# Sheet1.net
KiCad netlist of a schematic drawn in Altium Designer
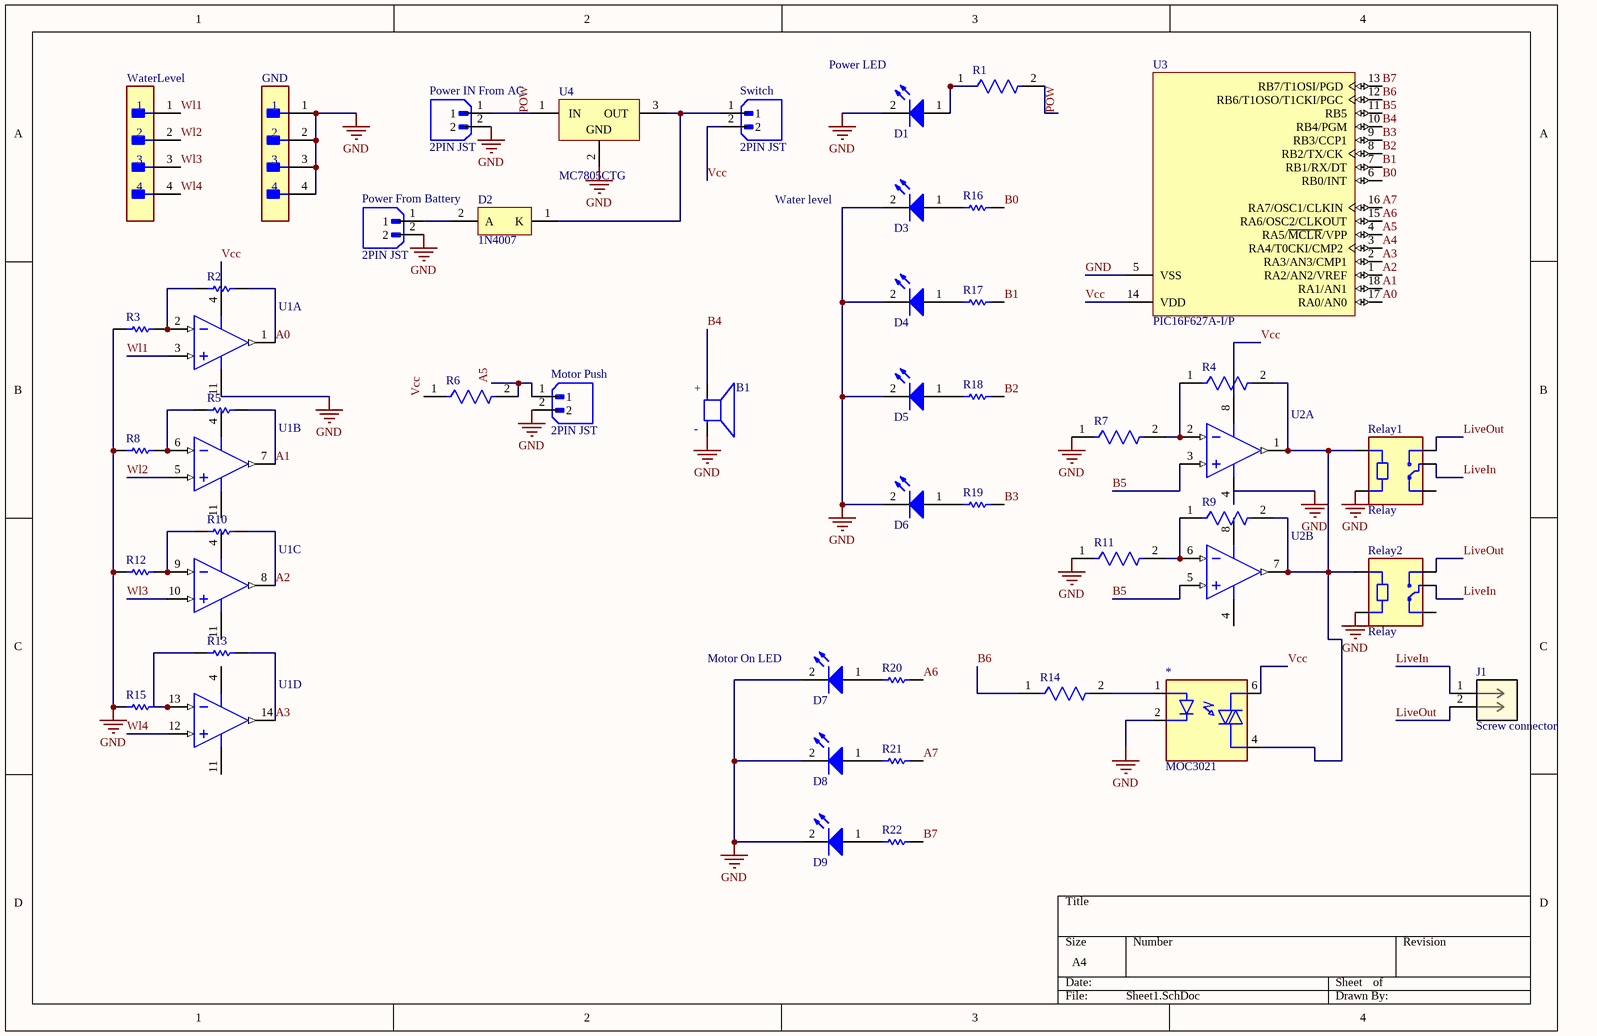
[diagram p0: Sheet1.SchDoc]

(export (version "E")
  (design (tool "Eeschema 10.0.6"))
  (components
    (comp (ref "*") (value "MOC3021") (footprint "MOC3021") (libsource (lib "Analogprj") (part "MOC3021")))
    (comp (ref "B1") (value "Buzzer") (footprint "Buzzer") (libsource (lib "Analogprj") (part "Buzzer")))
    (comp (ref "D1")
      (value "151051BS04000")
      (footprint "WL-TMRC_D5.9H8.7")
      (libsource (lib "Altium Content Vault") (part "LED_Blue_1A-2K"))
    )
    (comp (ref "D2")
      (value "1N4007")
      (footprint "ONSC-AXIAL_LEAD-2-59-10_P")
      (description "Standard Recovery Rectifier, 2-Pin Axial_Lead, Pb-Free, Bulk Bag")
      (fields (field (name "MANUFACTURER") "On Semiconductor"))
      (libsource (lib "Altium Content Vault") (part "ONSC-D-K1A2-2_A"))
    )
    (comp (ref "D3")
      (value "151051BS04000")
      (footprint "WL-TMRC_D5.9H8.7")
      (libsource (lib "Altium Content Vault") (part "LED_Blue_1A-2K"))
    )
    (comp (ref "D4")
      (value "151051BS04000")
      (footprint "WL-TMRC_D5.9H8.7")
      (libsource (lib "Altium Content Vault") (part "LED_Blue_1A-2K"))
    )
    (comp (ref "D5")
      (value "151051BS04000")
      (footprint "WL-TMRC_D5.9H8.7")
      (libsource (lib "Altium Content Vault") (part "LED_Blue_1A-2K"))
    )
    (comp (ref "D6")
      (value "151051BS04000")
      (footprint "WL-TMRC_D5.9H8.7")
      (libsource (lib "Altium Content Vault") (part "LED_Blue_1A-2K"))
    )
    (comp (ref "D7")
      (value "151051BS04000")
      (footprint "WL-TMRC_D5.9H8.7")
      (libsource (lib "Altium Content Vault") (part "LED_Blue_1A-2K"))
    )
    (comp (ref "D8")
      (value "151051BS04000")
      (footprint "WL-TMRC_D5.9H8.7")
      (libsource (lib "Altium Content Vault") (part "LED_Blue_1A-2K"))
    )
    (comp (ref "D9")
      (value "151051BS04000")
      (footprint "WL-TMRC_D5.9H8.7")
      (libsource (lib "Altium Content Vault") (part "LED_Blue_1A-2K"))
    )
    (comp (ref "GND")
      (value "B4B-XH-A(LF)(SN)")
      (footprint "FP-B4B-XH-A_LF_SN-MFG")
      (description "CONN HEADER VERT 4POS 2.5MM")
      (libsource (lib "Altium Content Vault") (part "299a8cea1bdcbc3624fe62c390fa72c"))
    )
    (comp (ref "J1")
      (value "Screw connector")
      (footprint "Screw Connector")
      (libsource (lib "Analogprj") (part "Screw connector"))
    )
    (comp (ref "Motor Push")
      (value "2PIN JST")
      (footprint "JST 2PIN")
      (libsource (lib "") (part "2PIN JST_1"))
    )
    (comp (ref "Power From Battery")
      (value "2PIN JST")
      (footprint "JST 2PIN")
      (libsource (lib "Analogprj") (part "2PIN JST"))
    )
    (comp (ref "Power IN From AC")
      (value "2PIN JST")
      (footprint "JST 2PIN")
      (libsource (lib "Analogprj") (part "2PIN JST"))
    )
    (comp (ref "R1")
      (value "MRS25000C1001FCT00")
      (footprint "FP-MRS25-MFG")
      (description "RES 1K OHM 0.6W 1% AXIAL")
      (fields (field (name "TOLERANCE") "1%"))
      (libsource (lib "Altium Content Vault") (part "1029c3af85768c4190bb7ad29bc67b5"))
    )
    (comp (ref "R2")
      (value "RC0805FR-071KL")
      (footprint "RESC2013X60X35ML10T20")
      (description "Chip Resistor, 1 KOhm, +/- 1%, 125 mW, -55 to 155 degC, 0805 (2012 Metric), RoHS, Tape and Reel")
      (fields (field (name "TOLERANCE") "1%") (field (name "MANUFACTURER") "Yageo"))
      (libsource (lib "Altium Content Vault") (part "RES-2"))
    )
    (comp (ref "R3")
      (value "RC0805FR-071KL")
      (footprint "RESC2013X60X35ML10T20")
      (description "Chip Resistor, 1 KOhm, +/- 1%, 125 mW, -55 to 155 degC, 0805 (2012 Metric), RoHS, Tape and Reel")
      (fields (field (name "TOLERANCE") "1%") (field (name "MANUFACTURER") "Yageo"))
      (libsource (lib "Altium Content Vault") (part "RES-2"))
    )
    (comp (ref "R4")
      (value "MRS25000C1001FCT00")
      (footprint "FP-MRS25-MFG")
      (description "RES 1K OHM 0.6W 1% AXIAL")
      (fields (field (name "TOLERANCE") "1%"))
      (libsource (lib "Altium Content Vault") (part "1029c3af85768c4190bb7ad29bc67b5"))
    )
    (comp (ref "R5")
      (value "RC0805FR-071KL")
      (footprint "RESC2013X60X35ML10T20")
      (description "Chip Resistor, 1 KOhm, +/- 1%, 125 mW, -55 to 155 degC, 0805 (2012 Metric), RoHS, Tape and Reel")
      (fields (field (name "TOLERANCE") "1%") (field (name "MANUFACTURER") "Yageo"))
      (libsource (lib "Altium Content Vault") (part "RES-2"))
    )
    (comp (ref "R6")
      (value "MRS25000C1001FCT00")
      (footprint "FP-MRS25-MFG")
      (description "100K")
      (fields (field (name "TOLERANCE") "1%"))
      (libsource (lib "Altium Content Vault") (part "1029c3af85768c4190bb7ad29bc67b5"))
    )
    (comp (ref "R7")
      (value "MRS25000C1001FCT00")
      (footprint "FP-MRS25-MFG")
      (description "RES 1K OHM 0.6W 1% AXIAL")
      (fields (field (name "TOLERANCE") "1%"))
      (libsource (lib "Altium Content Vault") (part "1029c3af85768c4190bb7ad29bc67b5"))
    )
    (comp (ref "R8")
      (value "RC0805FR-071KL")
      (footprint "RESC2013X60X35ML10T20")
      (description "Chip Resistor, 1 KOhm, +/- 1%, 125 mW, -55 to 155 degC, 0805 (2012 Metric), RoHS, Tape and Reel")
      (fields (field (name "TOLERANCE") "1%") (field (name "MANUFACTURER") "Yageo"))
      (libsource (lib "Altium Content Vault") (part "RES-2"))
    )
    (comp (ref "R9")
      (value "MRS25000C1001FCT00")
      (footprint "FP-MRS25-MFG")
      (description "RES 1K OHM 0.6W 1% AXIAL")
      (fields (field (name "TOLERANCE") "1%"))
      (libsource (lib "Altium Content Vault") (part "1029c3af85768c4190bb7ad29bc67b5"))
    )
    (comp (ref "R10")
      (value "RC0805FR-071KL")
      (footprint "RESC2013X60X35ML10T20")
      (description "Chip Resistor, 1 KOhm, +/- 1%, 125 mW, -55 to 155 degC, 0805 (2012 Metric), RoHS, Tape and Reel")
      (fields (field (name "TOLERANCE") "1%") (field (name "MANUFACTURER") "Yageo"))
      (libsource (lib "Altium Content Vault") (part "RES-2"))
    )
    (comp (ref "R11")
      (value "MRS25000C1001FCT00")
      (footprint "FP-MRS25-MFG")
      (description "RES 1K OHM 0.6W 1% AXIAL")
      (fields (field (name "TOLERANCE") "1%"))
      (libsource (lib "Altium Content Vault") (part "1029c3af85768c4190bb7ad29bc67b5"))
    )
    (comp (ref "R12")
      (value "RC0805FR-071KL")
      (footprint "RESC2013X60X35ML10T20")
      (description "Chip Resistor, 1 KOhm, +/- 1%, 125 mW, -55 to 155 degC, 0805 (2012 Metric), RoHS, Tape and Reel")
      (fields (field (name "TOLERANCE") "1%") (field (name "MANUFACTURER") "Yageo"))
      (libsource (lib "Altium Content Vault") (part "RES-2"))
    )
    (comp (ref "R13")
      (value "RC0805FR-071KL")
      (footprint "RESC2013X60X35ML10T20")
      (description "Chip Resistor, 1 KOhm, +/- 1%, 125 mW, -55 to 155 degC, 0805 (2012 Metric), RoHS, Tape and Reel")
      (fields (field (name "TOLERANCE") "1%") (field (name "MANUFACTURER") "Yageo"))
      (libsource (lib "Altium Content Vault") (part "RES-2"))
    )
    (comp (ref "R14")
      (value "MRS25000C1001FCT00")
      (footprint "FP-MRS25-MFG")
      (description "RES 1K OHM 0.6W 1% AXIAL")
      (fields (field (name "TOLERANCE") "1%"))
      (libsource (lib "Altium Content Vault") (part "1029c3af85768c4190bb7ad29bc67b5"))
    )
    (comp (ref "R15")
      (value "RC0805FR-071KL")
      (footprint "RESC2013X60X35ML10T20")
      (description "Chip Resistor, 1 KOhm, +/- 1%, 125 mW, -55 to 155 degC, 0805 (2012 Metric), RoHS, Tape and Reel")
      (fields (field (name "TOLERANCE") "1%") (field (name "MANUFACTURER") "Yageo"))
      (libsource (lib "Altium Content Vault") (part "RES-2"))
    )
    (comp (ref "R16")
      (value "RC0805FR-071KL")
      (footprint "RESC2013X60X35ML10T20")
      (description "Chip Resistor, 1 KOhm, +/- 1%, 125 mW, -55 to 155 degC, 0805 (2012 Metric), RoHS, Tape and Reel")
      (fields (field (name "TOLERANCE") "1%") (field (name "MANUFACTURER") "Yageo"))
      (libsource (lib "Altium Content Vault") (part "RES-2"))
    )
    (comp (ref "R17")
      (value "RC0805FR-071KL")
      (footprint "RESC2013X60X35ML10T20")
      (description "Chip Resistor, 1 KOhm, +/- 1%, 125 mW, -55 to 155 degC, 0805 (2012 Metric), RoHS, Tape and Reel")
      (fields (field (name "TOLERANCE") "1%") (field (name "MANUFACTURER") "Yageo"))
      (libsource (lib "Altium Content Vault") (part "RES-2"))
    )
    (comp (ref "R18")
      (value "RC0805FR-071KL")
      (footprint "RESC2013X60X35ML10T20")
      (description "Chip Resistor, 1 KOhm, +/- 1%, 125 mW, -55 to 155 degC, 0805 (2012 Metric), RoHS, Tape and Reel")
      (fields (field (name "TOLERANCE") "1%") (field (name "MANUFACTURER") "Yageo"))
      (libsource (lib "Altium Content Vault") (part "RES-2"))
    )
    (comp (ref "R19")
      (value "RC0805FR-071KL")
      (footprint "RESC2013X60X35ML10T20")
      (description "Chip Resistor, 1 KOhm, +/- 1%, 125 mW, -55 to 155 degC, 0805 (2012 Metric), RoHS, Tape and Reel")
      (fields (field (name "TOLERANCE") "1%") (field (name "MANUFACTURER") "Yageo"))
      (libsource (lib "Altium Content Vault") (part "RES-2"))
    )
    (comp (ref "R20")
      (value "RC0805FR-071KL")
      (footprint "RESC2013X60X35ML10T20")
      (description "Chip Resistor, 1 KOhm, +/- 1%, 125 mW, -55 to 155 degC, 0805 (2012 Metric), RoHS, Tape and Reel")
      (fields (field (name "TOLERANCE") "1%") (field (name "MANUFACTURER") "Yageo"))
      (libsource (lib "Altium Content Vault") (part "RES-2"))
    )
    (comp (ref "R21")
      (value "RC0805FR-071KL")
      (footprint "RESC2013X60X35ML10T20")
      (description "Chip Resistor, 1 KOhm, +/- 1%, 125 mW, -55 to 155 degC, 0805 (2012 Metric), RoHS, Tape and Reel")
      (fields (field (name "TOLERANCE") "1%") (field (name "MANUFACTURER") "Yageo"))
      (libsource (lib "Altium Content Vault") (part "RES-2"))
    )
    (comp (ref "R22")
      (value "RC0805FR-071KL")
      (footprint "RESC2013X60X35ML10T20")
      (description "Chip Resistor, 1 KOhm, +/- 1%, 125 mW, -55 to 155 degC, 0805 (2012 Metric), RoHS, Tape and Reel")
      (fields (field (name "TOLERANCE") "1%") (field (name "MANUFACTURER") "Yageo"))
      (libsource (lib "Altium Content Vault") (part "RES-2"))
    )
    (comp (ref "Relay1") (value "Relay") (footprint "Relay") (libsource (lib "Analogprj") (part "Relay")))
    (comp (ref "Relay2") (value "Relay") (footprint "Relay") (libsource (lib "Analogprj") (part "Relay")))
    (comp (ref "Switch") (value "2PIN JST") (footprint "JST 2PIN") (libsource (lib "") (part "2PIN JST_1")))
    (comp (ref "U1")
      (value "LMV324IDR")
      (footprint "D0014A_V")
      (libsource (lib "Altium Content Vault") (part "TI-LMV324-D-14"))
    )
    (comp (ref "U2")
      (value "LM358MX")
      (footprint "D0008A_M")
      (description "Low Power Dual Operational Amplifier, 8-pin Narrow SOIC")
      (fields (field (name "MANUFACTURER") "Texas Instruments"))
      (libsource (lib "Altium Content Vault") (part "AMP-OPA-LM158-8"))
    )
    (comp (ref "U3")
      (value "PIC16F627A-I/P")
      (footprint "PDIP300-P18")
      (libsource (lib "Altium Content Vault") (part "MC-8B-16F627A-IL18"))
    )
    (comp (ref "U4")
      (value "MC7805CTG")
      (footprint "ONSC-TO-220-3-221AB-01")
      (description "Positive Voltage Regulator, 1 A, 5 V, 0 to 125 degC, 3-Pin TO-220, RoHS, Tube")
      (fields (field (name "MANUFACTURER") "ON Semiconductor"))
      (libsource (lib "Altium Content Vault") (part "ONSC-MC7805CTG-TO-220-3"))
    )
    (comp (ref "WaterLevel")
      (value "B4B-XH-A(LF)(SN)")
      (footprint "FP-B4B-XH-A_LF_SN-MFG")
      (description "CONN HEADER VERT 4POS 2.5MM")
      (libsource (lib "Altium Content Vault") (part "299a8cea1bdcbc3624fe62c390fa72c"))
    )
  )
  (nets
    (net (code "1") (name "/A0") (class "Default")
      (node (ref "R2") (pin "2") (pinfunction "2_2") (pintype "passive"))
      (node (ref "U1") (pin "1") (pinfunction "1OUT_1") (pintype "output"))
      (node (ref "U3") (pin "17") (pinfunction "RA0/AN0_17") (pintype "bidirectional"))
    )
    (net (code "2") (name "/A1") (class "Default")
      (node (ref "R5") (pin "2") (pinfunction "2_2") (pintype "passive"))
      (node (ref "U1") (pin "7") (pinfunction "2OUT_7") (pintype "output"))
      (node (ref "U3") (pin "18") (pinfunction "RA1/AN1_18") (pintype "bidirectional"))
    )
    (net (code "3") (name "/A2") (class "Default")
      (node (ref "R10") (pin "2") (pinfunction "2_2") (pintype "passive"))
      (node (ref "U1") (pin "8") (pinfunction "3OUT_8") (pintype "output"))
      (node (ref "U3") (pin "1") (pinfunction "RA2/AN2/VREF_1") (pintype "bidirectional"))
    )
    (net (code "4") (name "/A3") (class "Default")
      (node (ref "R13") (pin "2") (pinfunction "2_2") (pintype "passive"))
      (node (ref "U1") (pin "14") (pinfunction "4OUT_14") (pintype "output"))
      (node (ref "U3") (pin "2") (pinfunction "RA3/AN3/CMP1_2") (pintype "bidirectional"))
    )
    (net (code "5") (name "/A4") (class "Default")
      (node (ref "U3") (pin "3") (pinfunction "RA4/T0CKI/CMP2_3") (pintype "bidirectional"))
    )
    (net (code "6") (name "/A5") (class "Default")
      (node (ref "Motor Push") (pin "1") (pinfunction "1_1") (pintype "passive"))
      (node (ref "R6") (pin "2") (pinfunction "2_2") (pintype "passive"))
      (node (ref "U3") (pin "4") (pinfunction "RA5/~{MCLR}/VPP_4") (pintype "bidirectional"))
    )
    (net (code "7") (name "/A6") (class "Default")
      (node (ref "R20") (pin "2") (pinfunction "2_2") (pintype "passive"))
      (node (ref "U3") (pin "15") (pinfunction "RA6/OSC2/CLKOUT_15") (pintype "bidirectional"))
    )
    (net (code "8") (name "/A7") (class "Default")
      (node (ref "R21") (pin "2") (pinfunction "2_2") (pintype "passive"))
      (node (ref "U3") (pin "16") (pinfunction "RA7/OSC1/CLKIN_16") (pintype "bidirectional"))
    )
    (net (code "9") (name "/B0") (class "Default")
      (node (ref "R16") (pin "2") (pinfunction "2_2") (pintype "passive"))
      (node (ref "U3") (pin "6") (pinfunction "RB0/INT_6") (pintype "bidirectional"))
    )
    (net (code "10") (name "/B1") (class "Default")
      (node (ref "R17") (pin "2") (pinfunction "2_2") (pintype "passive"))
      (node (ref "U3") (pin "7") (pinfunction "RB1/RX/DT_7") (pintype "bidirectional"))
    )
    (net (code "11") (name "/B2") (class "Default")
      (node (ref "R18") (pin "2") (pinfunction "2_2") (pintype "passive"))
      (node (ref "U3") (pin "8") (pinfunction "RB2/TX/CK_8") (pintype "bidirectional"))
    )
    (net (code "12") (name "/B3") (class "Default")
      (node (ref "R19") (pin "2") (pinfunction "2_2") (pintype "passive"))
      (node (ref "U3") (pin "9") (pinfunction "RB3/CCP1_9") (pintype "bidirectional"))
    )
    (net (code "13") (name "/B4") (class "Default")
      (node (ref "B1") (pin "P") (pinfunction "P_P") (pintype "passive"))
      (node (ref "U3") (pin "10") (pinfunction "RB4/PGM_10") (pintype "bidirectional"))
    )
    (net (code "14") (name "/B5") (class "Default")
      (node (ref "U2") (pin "3") (pinfunction "INA+_3") (pintype "input"))
      (node (ref "U2") (pin "5") (pinfunction "INB+_5") (pintype "input"))
      (node (ref "U3") (pin "11") (pinfunction "RB5_11") (pintype "bidirectional"))
    )
    (net (code "15") (name "/B6") (class "Default")
      (node (ref "R14") (pin "1") (pinfunction "1_1") (pintype "passive"))
      (node (ref "U3") (pin "12") (pinfunction "RB6/T1OSO/T1CKI/PGC_12") (pintype "bidirectional"))
    )
    (net (code "16") (name "/B7") (class "Default")
      (node (ref "R22") (pin "2") (pinfunction "2_2") (pintype "passive"))
      (node (ref "U3") (pin "13") (pinfunction "RB7/T1OSI/PGD_13") (pintype "bidirectional"))
    )
    (net (code "17") (name "/LiveIn") (class "Default")
      (node (ref "J1") (pin "1") (pinfunction "1_1") (pintype "passive"))
      (node (ref "Relay1") (pin "COM") (pinfunction "COM_COM") (pintype "passive"))
      (node (ref "Relay2") (pin "COM") (pinfunction "COM_COM") (pintype "passive"))
    )
    (net (code "18") (name "/LiveOut") (class "Default")
      (node (ref "J1") (pin "2") (pinfunction "2_2") (pintype "passive"))
      (node (ref "Relay1") (pin "NO") (pinfunction "NO_NO") (pintype "passive"))
      (node (ref "Relay2") (pin "NO") (pinfunction "NO_NO") (pintype "passive"))
    )
    (net (code "19") (name "/POW") (class "Default")
      (node (ref "Power IN From AC") (pin "1") (pinfunction "1_1") (pintype "passive"))
      (node (ref "R1") (pin "2") (pinfunction "2_2") (pintype "passive"))
      (node (ref "U4") (pin "1") (pinfunction "IN_1") (pintype "power_in"))
    )
    (net (code "20") (name "/Vcc") (class "Default")
      (node (ref "*") (pin "6") (pinfunction "MAIN_TERM1_6") (pintype "passive"))
      (node (ref "R6") (pin "1") (pinfunction "1_1") (pintype "passive"))
      (node (ref "Switch") (pin "2") (pinfunction "2_2") (pintype "passive"))
      (node (ref "U1") (pin "4") (pinfunction "VCC+_4") (pintype "power_in"))
      (node (ref "U2") (pin "8") (pinfunction "V+_8") (pintype "power_in"))
      (node (ref "U3") (pin "14") (pinfunction "VDD_14") (pintype "power_in"))
    )
    (net (code "21") (name "/Wl1") (class "Default")
      (node (ref "U1") (pin "3") (pinfunction "1IN+_3") (pintype "input"))
      (node (ref "WaterLevel") (pin "1") (pinfunction "1_1") (pintype "passive"))
    )
    (net (code "22") (name "/Wl2") (class "Default")
      (node (ref "U1") (pin "5") (pinfunction "2IN+_5") (pintype "input"))
      (node (ref "WaterLevel") (pin "2") (pinfunction "2_2") (pintype "passive"))
    )
    (net (code "23") (name "/Wl3") (class "Default")
      (node (ref "U1") (pin "10") (pinfunction "3IN+_10") (pintype "input"))
      (node (ref "WaterLevel") (pin "3") (pinfunction "3_3") (pintype "passive"))
    )
    (net (code "24") (name "/Wl4") (class "Default")
      (node (ref "U1") (pin "12") (pinfunction "4IN+_12") (pintype "input"))
      (node (ref "WaterLevel") (pin "4") (pinfunction "4_4") (pintype "passive"))
    )
    (net (code "25") (name "GND") (class "Default")
      (node (ref "*") (pin "2") (pinfunction "CATODE_2") (pintype "passive"))
      (node (ref "B1") (pin "N") (pinfunction "N_N") (pintype "passive"))
      (node (ref "D1") (pin "2") (pinfunction "K_2") (pintype "passive"))
      (node (ref "D3") (pin "2") (pinfunction "K_2") (pintype "passive"))
      (node (ref "D4") (pin "2") (pinfunction "K_2") (pintype "passive"))
      (node (ref "D5") (pin "2") (pinfunction "K_2") (pintype "passive"))
      (node (ref "D6") (pin "2") (pinfunction "K_2") (pintype "passive"))
      (node (ref "D7") (pin "2") (pinfunction "K_2") (pintype "passive"))
      (node (ref "D8") (pin "2") (pinfunction "K_2") (pintype "passive"))
      (node (ref "D9") (pin "2") (pinfunction "K_2") (pintype "passive"))
      (node (ref "GND") (pin "1") (pinfunction "1_1") (pintype "passive"))
      (node (ref "GND") (pin "2") (pinfunction "2_2") (pintype "passive"))
      (node (ref "GND") (pin "3") (pinfunction "3_3") (pintype "passive"))
      (node (ref "GND") (pin "4") (pinfunction "4_4") (pintype "passive"))
      (node (ref "Motor Push") (pin "2") (pinfunction "2_2") (pintype "passive"))
      (node (ref "Power From Battery") (pin "2") (pinfunction "2_2") (pintype "passive"))
      (node (ref "Power IN From AC") (pin "2") (pinfunction "2_2") (pintype "passive"))
      (node (ref "R11") (pin "1") (pinfunction "1_1") (pintype "passive"))
      (node (ref "R12") (pin "1") (pinfunction "1_1") (pintype "passive"))
      (node (ref "R15") (pin "1") (pinfunction "1_1") (pintype "passive"))
      (node (ref "R3") (pin "1") (pinfunction "1_1") (pintype "passive"))
      (node (ref "R7") (pin "1") (pinfunction "1_1") (pintype "passive"))
      (node (ref "R8") (pin "1") (pinfunction "1_1") (pintype "passive"))
      (node (ref "Relay1") (pin "A2") (pinfunction "A2_A2") (pintype "passive"))
      (node (ref "Relay2") (pin "A2") (pinfunction "A2_A2") (pintype "passive"))
      (node (ref "U1") (pin "11") (pinfunction "GND_11") (pintype "power_in"))
      (node (ref "U2") (pin "4") (pinfunction "GND_4") (pintype "power_in"))
      (node (ref "U3") (pin "5") (pinfunction "VSS_5") (pintype "power_in"))
      (node (ref "U4") (pin "2") (pinfunction "GND_2") (pintype "power_in"))
    )
    (net (code "26") (name "Net-(*-ANODE)") (class "Default")
      (node (ref "*") (pin "1") (pinfunction "ANODE_1") (pintype "passive"))
      (node (ref "R14") (pin "2") (pinfunction "2_2") (pintype "passive"))
    )
    (net (code "27") (name "Net-(*-MAIN_TERM2)") (class "Default")
      (node (ref "*") (pin "4") (pinfunction "MAIN_TERM2_4") (pintype "passive"))
      (node (ref "R4") (pin "2") (pinfunction "2_2") (pintype "passive"))
      (node (ref "R9") (pin "2") (pinfunction "2_2") (pintype "passive"))
      (node (ref "Relay1") (pin "A1") (pinfunction "A1_A1") (pintype "passive"))
      (node (ref "Relay2") (pin "A1") (pinfunction "A1_A1") (pintype "passive"))
      (node (ref "U2") (pin "1") (pinfunction "OUTA_1") (pintype "output"))
      (node (ref "U2") (pin "7") (pinfunction "OUTB_7") (pintype "output"))
    )
    (net (code "28") (name "Net-(D1-A)") (class "Default")
      (node (ref "D1") (pin "1") (pinfunction "A_1") (pintype "passive"))
      (node (ref "R1") (pin "1") (pinfunction "1_1") (pintype "passive"))
    )
    (net (code "29") (name "Net-(D2-A)") (class "Default")
      (node (ref "D2") (pin "2") (pinfunction "A_2") (pintype "passive"))
      (node (ref "Power From Battery") (pin "1") (pinfunction "1_1") (pintype "passive"))
    )
    (net (code "30") (name "Net-(D2-K)") (class "Default")
      (node (ref "D2") (pin "1") (pinfunction "K_1") (pintype "passive"))
      (node (ref "Switch") (pin "1") (pinfunction "1_1") (pintype "passive"))
      (node (ref "U4") (pin "3") (pinfunction "OUT_3") (pintype "power_in"))
    )
    (net (code "31") (name "Net-(D3-A)") (class "Default")
      (node (ref "D3") (pin "1") (pinfunction "A_1") (pintype "passive"))
      (node (ref "R16") (pin "1") (pinfunction "1_1") (pintype "passive"))
    )
    (net (code "32") (name "Net-(D4-A)") (class "Default")
      (node (ref "D4") (pin "1") (pinfunction "A_1") (pintype "passive"))
      (node (ref "R17") (pin "1") (pinfunction "1_1") (pintype "passive"))
    )
    (net (code "33") (name "Net-(D5-A)") (class "Default")
      (node (ref "D5") (pin "1") (pinfunction "A_1") (pintype "passive"))
      (node (ref "R18") (pin "1") (pinfunction "1_1") (pintype "passive"))
    )
    (net (code "34") (name "Net-(D6-A)") (class "Default")
      (node (ref "D6") (pin "1") (pinfunction "A_1") (pintype "passive"))
      (node (ref "R19") (pin "1") (pinfunction "1_1") (pintype "passive"))
    )
    (net (code "35") (name "Net-(D7-A)") (class "Default")
      (node (ref "D7") (pin "1") (pinfunction "A_1") (pintype "passive"))
      (node (ref "R20") (pin "1") (pinfunction "1_1") (pintype "passive"))
    )
    (net (code "36") (name "Net-(D8-A)") (class "Default")
      (node (ref "D8") (pin "1") (pinfunction "A_1") (pintype "passive"))
      (node (ref "R21") (pin "1") (pinfunction "1_1") (pintype "passive"))
    )
    (net (code "37") (name "Net-(D9-A)") (class "Default")
      (node (ref "D9") (pin "1") (pinfunction "A_1") (pintype "passive"))
      (node (ref "R22") (pin "1") (pinfunction "1_1") (pintype "passive"))
    )
    (net (code "38") (name "Net-(U1A-1IN-)") (class "Default")
      (node (ref "R2") (pin "1") (pinfunction "1_1") (pintype "passive"))
      (node (ref "R3") (pin "2") (pinfunction "2_2") (pintype "passive"))
      (node (ref "U1") (pin "2") (pinfunction "1IN-_2") (pintype "input"))
    )
    (net (code "39") (name "Net-(U1B-2IN-)") (class "Default")
      (node (ref "R5") (pin "1") (pinfunction "1_1") (pintype "passive"))
      (node (ref "R8") (pin "2") (pinfunction "2_2") (pintype "passive"))
      (node (ref "U1") (pin "6") (pinfunction "2IN-_6") (pintype "input"))
    )
    (net (code "40") (name "Net-(U1C-3IN-)") (class "Default")
      (node (ref "R10") (pin "1") (pinfunction "1_1") (pintype "passive"))
      (node (ref "R12") (pin "2") (pinfunction "2_2") (pintype "passive"))
      (node (ref "U1") (pin "9") (pinfunction "3IN-_9") (pintype "input"))
    )
    (net (code "41") (name "Net-(U1D-4IN-)") (class "Default")
      (node (ref "R13") (pin "1") (pinfunction "1_1") (pintype "passive"))
      (node (ref "R15") (pin "2") (pinfunction "2_2") (pintype "passive"))
      (node (ref "U1") (pin "13") (pinfunction "4IN-_13") (pintype "input"))
    )
    (net (code "42") (name "Net-(U2A-INA-)") (class "Default")
      (node (ref "R4") (pin "1") (pinfunction "1_1") (pintype "passive"))
      (node (ref "R7") (pin "2") (pinfunction "2_2") (pintype "passive"))
      (node (ref "U2") (pin "2") (pinfunction "INA-_2") (pintype "input"))
    )
    (net (code "43") (name "Net-(U2B-INB-)") (class "Default")
      (node (ref "R11") (pin "2") (pinfunction "2_2") (pintype "passive"))
      (node (ref "R9") (pin "1") (pinfunction "1_1") (pintype "passive"))
      (node (ref "U2") (pin "6") (pinfunction "INB-_6") (pintype "input"))
    )
    (net (code "44") (name "unconnected-(Relay1-PadNC)") (class "Default")
      (node (ref "Relay1") (pin "NC") (pinfunction "NC_NC") (pintype "passive"))
    )
    (net (code "45") (name "unconnected-(Relay2-PadNC)") (class "Default")
      (node (ref "Relay2") (pin "NC") (pinfunction "NC_NC") (pintype "passive"))
    )
    (net (code "46") (name "unconnected-(U1B-GND-Pad11)") (class "Default")
      (node (ref "U1") (pin "11") (pinfunction "GND_11") (pintype "power_in"))
    )
    (net (code "47") (name "unconnected-(U1B-VCC+-Pad4)") (class "Default")
      (node (ref "U1") (pin "4") (pinfunction "VCC+_4") (pintype "power_in"))
    )
    (net (code "48") (name "unconnected-(U1C-GND-Pad11)") (class "Default")
      (node (ref "U1") (pin "11") (pinfunction "GND_11") (pintype "power_in"))
    )
    (net (code "49") (name "unconnected-(U1C-VCC+-Pad4)") (class "Default")
      (node (ref "U1") (pin "4") (pinfunction "VCC+_4") (pintype "power_in"))
    )
    (net (code "50") (name "unconnected-(U1D-GND-Pad11)") (class "Default")
      (node (ref "U1") (pin "11") (pinfunction "GND_11") (pintype "power_in"))
    )
    (net (code "51") (name "unconnected-(U1D-VCC+-Pad4)") (class "Default")
      (node (ref "U1") (pin "4") (pinfunction "VCC+_4") (pintype "power_in"))
    )
    (net (code "52") (name "unconnected-(U2B-GND-Pad4)") (class "Default")
      (node (ref "U2") (pin "4") (pinfunction "GND_4") (pintype "power_in"))
    )
    (net (code "53") (name "unconnected-(U2B-V+-Pad8)") (class "Default")
      (node (ref "U2") (pin "8") (pinfunction "V+_8") (pintype "power_in"))
    )
  )
)
